# LED.net
KiCad netlist of a schematic drawn in Altium Designer
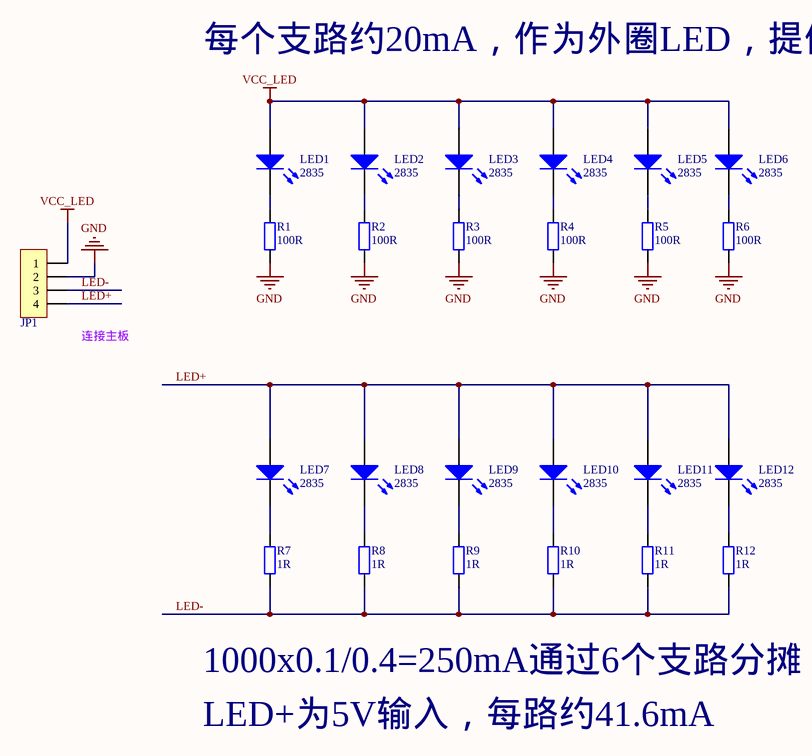
[diagram p0: LED.SchDoc]

(export (version "E")
  (design (tool "Eeschema 10.0.6"))
  (components
    (comp (ref "JP1")
      (value "HDR-1X4")
      (footprint "MX1.25-L-4P")
      (description "4P连接器")
      (libsource (lib "5.1 - 1.25mm连接器(FPC1.25_GH1.25_MX1.25)") (part "Header 4"))
    )
    (comp (ref "LED1")
      (value "2835")
      (footprint "LED 2835-2P")
      (description "0.2W 功率LED")
      (libsource (lib "0.3 - LED发光二极管-IR二极管_接收管-光耦") (part "LED-2835"))
    )
    (comp (ref "LED2")
      (value "2835")
      (footprint "LED 2835-2P")
      (description "0.2W 功率LED")
      (libsource (lib "0.3 - LED发光二极管-IR二极管_接收管-光耦") (part "LED-2835"))
    )
    (comp (ref "LED3")
      (value "2835")
      (footprint "LED 2835-2P")
      (description "0.2W 功率LED")
      (libsource (lib "0.3 - LED发光二极管-IR二极管_接收管-光耦") (part "LED-2835"))
    )
    (comp (ref "LED4")
      (value "2835")
      (footprint "LED 2835-2P")
      (description "0.2W 功率LED")
      (libsource (lib "0.3 - LED发光二极管-IR二极管_接收管-光耦") (part "LED-2835"))
    )
    (comp (ref "LED5")
      (value "2835")
      (footprint "LED 2835-2P")
      (description "0.2W 功率LED")
      (libsource (lib "0.3 - LED发光二极管-IR二极管_接收管-光耦") (part "LED-2835"))
    )
    (comp (ref "LED6")
      (value "2835")
      (footprint "LED 2835-2P")
      (description "0.2W 功率LED")
      (libsource (lib "0.3 - LED发光二极管-IR二极管_接收管-光耦") (part "LED-2835"))
    )
    (comp (ref "LED7")
      (value "2835")
      (footprint "LED 2835-2P")
      (description "0.2W 功率LED")
      (libsource (lib "0.3 - LED发光二极管-IR二极管_接收管-光耦") (part "LED-2835"))
    )
    (comp (ref "LED8")
      (value "2835")
      (footprint "LED 2835-2P")
      (description "0.2W 功率LED")
      (libsource (lib "0.3 - LED发光二极管-IR二极管_接收管-光耦") (part "LED-2835"))
    )
    (comp (ref "LED9")
      (value "2835")
      (footprint "LED 2835-2P")
      (description "0.2W 功率LED")
      (libsource (lib "0.3 - LED发光二极管-IR二极管_接收管-光耦") (part "LED-2835"))
    )
    (comp (ref "LED10")
      (value "2835")
      (footprint "LED 2835-2P")
      (description "0.2W 功率LED")
      (libsource (lib "0.3 - LED发光二极管-IR二极管_接收管-光耦") (part "LED-2835"))
    )
    (comp (ref "LED11")
      (value "2835")
      (footprint "LED 2835-2P")
      (description "0.2W 功率LED")
      (libsource (lib "0.3 - LED发光二极管-IR二极管_接收管-光耦") (part "LED-2835"))
    )
    (comp (ref "LED12")
      (value "2835")
      (footprint "LED 2835-2P")
      (description "0.2W 功率LED")
      (libsource (lib "0.3 - LED发光二极管-IR二极管_接收管-光耦") (part "LED-2835"))
    )
    (comp (ref "R1")
      (value "100R")
      (footprint "R0603_L")
      (description "贴片电阻")
      (libsource (lib "0.1 - 电阻-电容-电感-保险丝-晶振-晶体-磁珠-电位器-法拉电容-馈通电容") (part "R"))
    )
    (comp (ref "R2")
      (value "100R")
      (footprint "R0603_L")
      (description "贴片电阻")
      (libsource (lib "0.1 - 电阻-电容-电感-保险丝-晶振-晶体-磁珠-电位器-法拉电容-馈通电容") (part "R"))
    )
    (comp (ref "R3")
      (value "100R")
      (footprint "R0603_L")
      (description "贴片电阻")
      (libsource (lib "0.1 - 电阻-电容-电感-保险丝-晶振-晶体-磁珠-电位器-法拉电容-馈通电容") (part "R"))
    )
    (comp (ref "R4")
      (value "100R")
      (footprint "R0603_L")
      (description "贴片电阻")
      (libsource (lib "0.1 - 电阻-电容-电感-保险丝-晶振-晶体-磁珠-电位器-法拉电容-馈通电容") (part "R"))
    )
    (comp (ref "R5")
      (value "100R")
      (footprint "R0603_L")
      (description "贴片电阻")
      (libsource (lib "0.1 - 电阻-电容-电感-保险丝-晶振-晶体-磁珠-电位器-法拉电容-馈通电容") (part "R"))
    )
    (comp (ref "R6")
      (value "100R")
      (footprint "R0603_L")
      (description "贴片电阻")
      (libsource (lib "0.1 - 电阻-电容-电感-保险丝-晶振-晶体-磁珠-电位器-法拉电容-馈通电容") (part "R"))
    )
    (comp (ref "R7")
      (value "1R")
      (footprint "R1206_L")
      (description "贴片电阻")
      (libsource (lib "0.1 - 电阻-电容-电感-保险丝-晶振-晶体-磁珠-电位器-法拉电容-馈通电容") (part "R"))
    )
    (comp (ref "R8")
      (value "1R")
      (footprint "R1206_L")
      (description "贴片电阻")
      (libsource (lib "0.1 - 电阻-电容-电感-保险丝-晶振-晶体-磁珠-电位器-法拉电容-馈通电容") (part "R"))
    )
    (comp (ref "R9")
      (value "1R")
      (footprint "R1206_L")
      (description "贴片电阻")
      (libsource (lib "0.1 - 电阻-电容-电感-保险丝-晶振-晶体-磁珠-电位器-法拉电容-馈通电容") (part "R"))
    )
    (comp (ref "R10")
      (value "1R")
      (footprint "R1206_L")
      (description "贴片电阻")
      (libsource (lib "0.1 - 电阻-电容-电感-保险丝-晶振-晶体-磁珠-电位器-法拉电容-馈通电容") (part "R"))
    )
    (comp (ref "R11")
      (value "1R")
      (footprint "R1206_L")
      (description "贴片电阻")
      (libsource (lib "0.1 - 电阻-电容-电感-保险丝-晶振-晶体-磁珠-电位器-法拉电容-馈通电容") (part "R"))
    )
    (comp (ref "R12")
      (value "1R")
      (footprint "R1206_L")
      (description "贴片电阻")
      (libsource (lib "0.1 - 电阻-电容-电感-保险丝-晶振-晶体-磁珠-电位器-法拉电容-馈通电容") (part "R"))
    )
  )
  (nets
    (net (code "1") (name "/LED+") (class "Default")
      (node (ref "JP1") (pin "4") (pinfunction "4_4") (pintype "passive"))
      (node (ref "LED10") (pin "1") (pinfunction "A_1") (pintype "passive"))
      (node (ref "LED11") (pin "1") (pinfunction "A_1") (pintype "passive"))
      (node (ref "LED12") (pin "1") (pinfunction "A_1") (pintype "passive"))
      (node (ref "LED7") (pin "1") (pinfunction "A_1") (pintype "passive"))
      (node (ref "LED8") (pin "1") (pinfunction "A_1") (pintype "passive"))
      (node (ref "LED9") (pin "1") (pinfunction "A_1") (pintype "passive"))
    )
    (net (code "2") (name "/LED-") (class "Default")
      (node (ref "JP1") (pin "3") (pinfunction "3_3") (pintype "passive"))
      (node (ref "R10") (pin "1") (pinfunction "1_1") (pintype "passive"))
      (node (ref "R11") (pin "1") (pinfunction "1_1") (pintype "passive"))
      (node (ref "R12") (pin "1") (pinfunction "1_1") (pintype "passive"))
      (node (ref "R7") (pin "1") (pinfunction "1_1") (pintype "passive"))
      (node (ref "R8") (pin "1") (pinfunction "1_1") (pintype "passive"))
      (node (ref "R9") (pin "1") (pinfunction "1_1") (pintype "passive"))
    )
    (net (code "3") (name "GND") (class "Default")
      (node (ref "JP1") (pin "2") (pinfunction "2_2") (pintype "passive"))
      (node (ref "R1") (pin "1") (pinfunction "1_1") (pintype "passive"))
      (node (ref "R2") (pin "1") (pinfunction "1_1") (pintype "passive"))
      (node (ref "R3") (pin "1") (pinfunction "1_1") (pintype "passive"))
      (node (ref "R4") (pin "1") (pinfunction "1_1") (pintype "passive"))
      (node (ref "R5") (pin "1") (pinfunction "1_1") (pintype "passive"))
      (node (ref "R6") (pin "1") (pinfunction "1_1") (pintype "passive"))
    )
    (net (code "4") (name "Net-(LED1-K)") (class "Default")
      (node (ref "LED1") (pin "2") (pinfunction "K_2") (pintype "passive"))
      (node (ref "R1") (pin "2") (pinfunction "2_2") (pintype "passive"))
    )
    (net (code "5") (name "Net-(LED2-K)") (class "Default")
      (node (ref "LED2") (pin "2") (pinfunction "K_2") (pintype "passive"))
      (node (ref "R2") (pin "2") (pinfunction "2_2") (pintype "passive"))
    )
    (net (code "6") (name "Net-(LED3-K)") (class "Default")
      (node (ref "LED3") (pin "2") (pinfunction "K_2") (pintype "passive"))
      (node (ref "R3") (pin "2") (pinfunction "2_2") (pintype "passive"))
    )
    (net (code "7") (name "Net-(LED4-K)") (class "Default")
      (node (ref "LED4") (pin "2") (pinfunction "K_2") (pintype "passive"))
      (node (ref "R4") (pin "2") (pinfunction "2_2") (pintype "passive"))
    )
    (net (code "8") (name "Net-(LED5-K)") (class "Default")
      (node (ref "LED5") (pin "2") (pinfunction "K_2") (pintype "passive"))
      (node (ref "R5") (pin "2") (pinfunction "2_2") (pintype "passive"))
    )
    (net (code "9") (name "Net-(LED6-K)") (class "Default")
      (node (ref "LED6") (pin "2") (pinfunction "K_2") (pintype "passive"))
      (node (ref "R6") (pin "2") (pinfunction "2_2") (pintype "passive"))
    )
    (net (code "10") (name "Net-(LED7-K)") (class "Default")
      (node (ref "LED7") (pin "2") (pinfunction "K_2") (pintype "passive"))
      (node (ref "R7") (pin "2") (pinfunction "2_2") (pintype "passive"))
    )
    (net (code "11") (name "Net-(LED8-K)") (class "Default")
      (node (ref "LED8") (pin "2") (pinfunction "K_2") (pintype "passive"))
      (node (ref "R8") (pin "2") (pinfunction "2_2") (pintype "passive"))
    )
    (net (code "12") (name "Net-(LED9-K)") (class "Default")
      (node (ref "LED9") (pin "2") (pinfunction "K_2") (pintype "passive"))
      (node (ref "R9") (pin "2") (pinfunction "2_2") (pintype "passive"))
    )
    (net (code "13") (name "Net-(LED10-K)") (class "Default")
      (node (ref "LED10") (pin "2") (pinfunction "K_2") (pintype "passive"))
      (node (ref "R10") (pin "2") (pinfunction "2_2") (pintype "passive"))
    )
    (net (code "14") (name "Net-(LED11-K)") (class "Default")
      (node (ref "LED11") (pin "2") (pinfunction "K_2") (pintype "passive"))
      (node (ref "R11") (pin "2") (pinfunction "2_2") (pintype "passive"))
    )
    (net (code "15") (name "Net-(LED12-K)") (class "Default")
      (node (ref "LED12") (pin "2") (pinfunction "K_2") (pintype "passive"))
      (node (ref "R12") (pin "2") (pinfunction "2_2") (pintype "passive"))
    )
    (net (code "16") (name "VCC_LED") (class "Default")
      (node (ref "JP1") (pin "1") (pinfunction "1_1") (pintype "passive"))
      (node (ref "LED1") (pin "1") (pinfunction "A_1") (pintype "passive"))
      (node (ref "LED2") (pin "1") (pinfunction "A_1") (pintype "passive"))
      (node (ref "LED3") (pin "1") (pinfunction "A_1") (pintype "passive"))
      (node (ref "LED4") (pin "1") (pinfunction "A_1") (pintype "passive"))
      (node (ref "LED5") (pin "1") (pinfunction "A_1") (pintype "passive"))
      (node (ref "LED6") (pin "1") (pinfunction "A_1") (pintype "passive"))
    )
  )
)
